# BOOSTXL-AUDIO_Main.net
KiCad netlist of a schematic drawn in Altium Designer
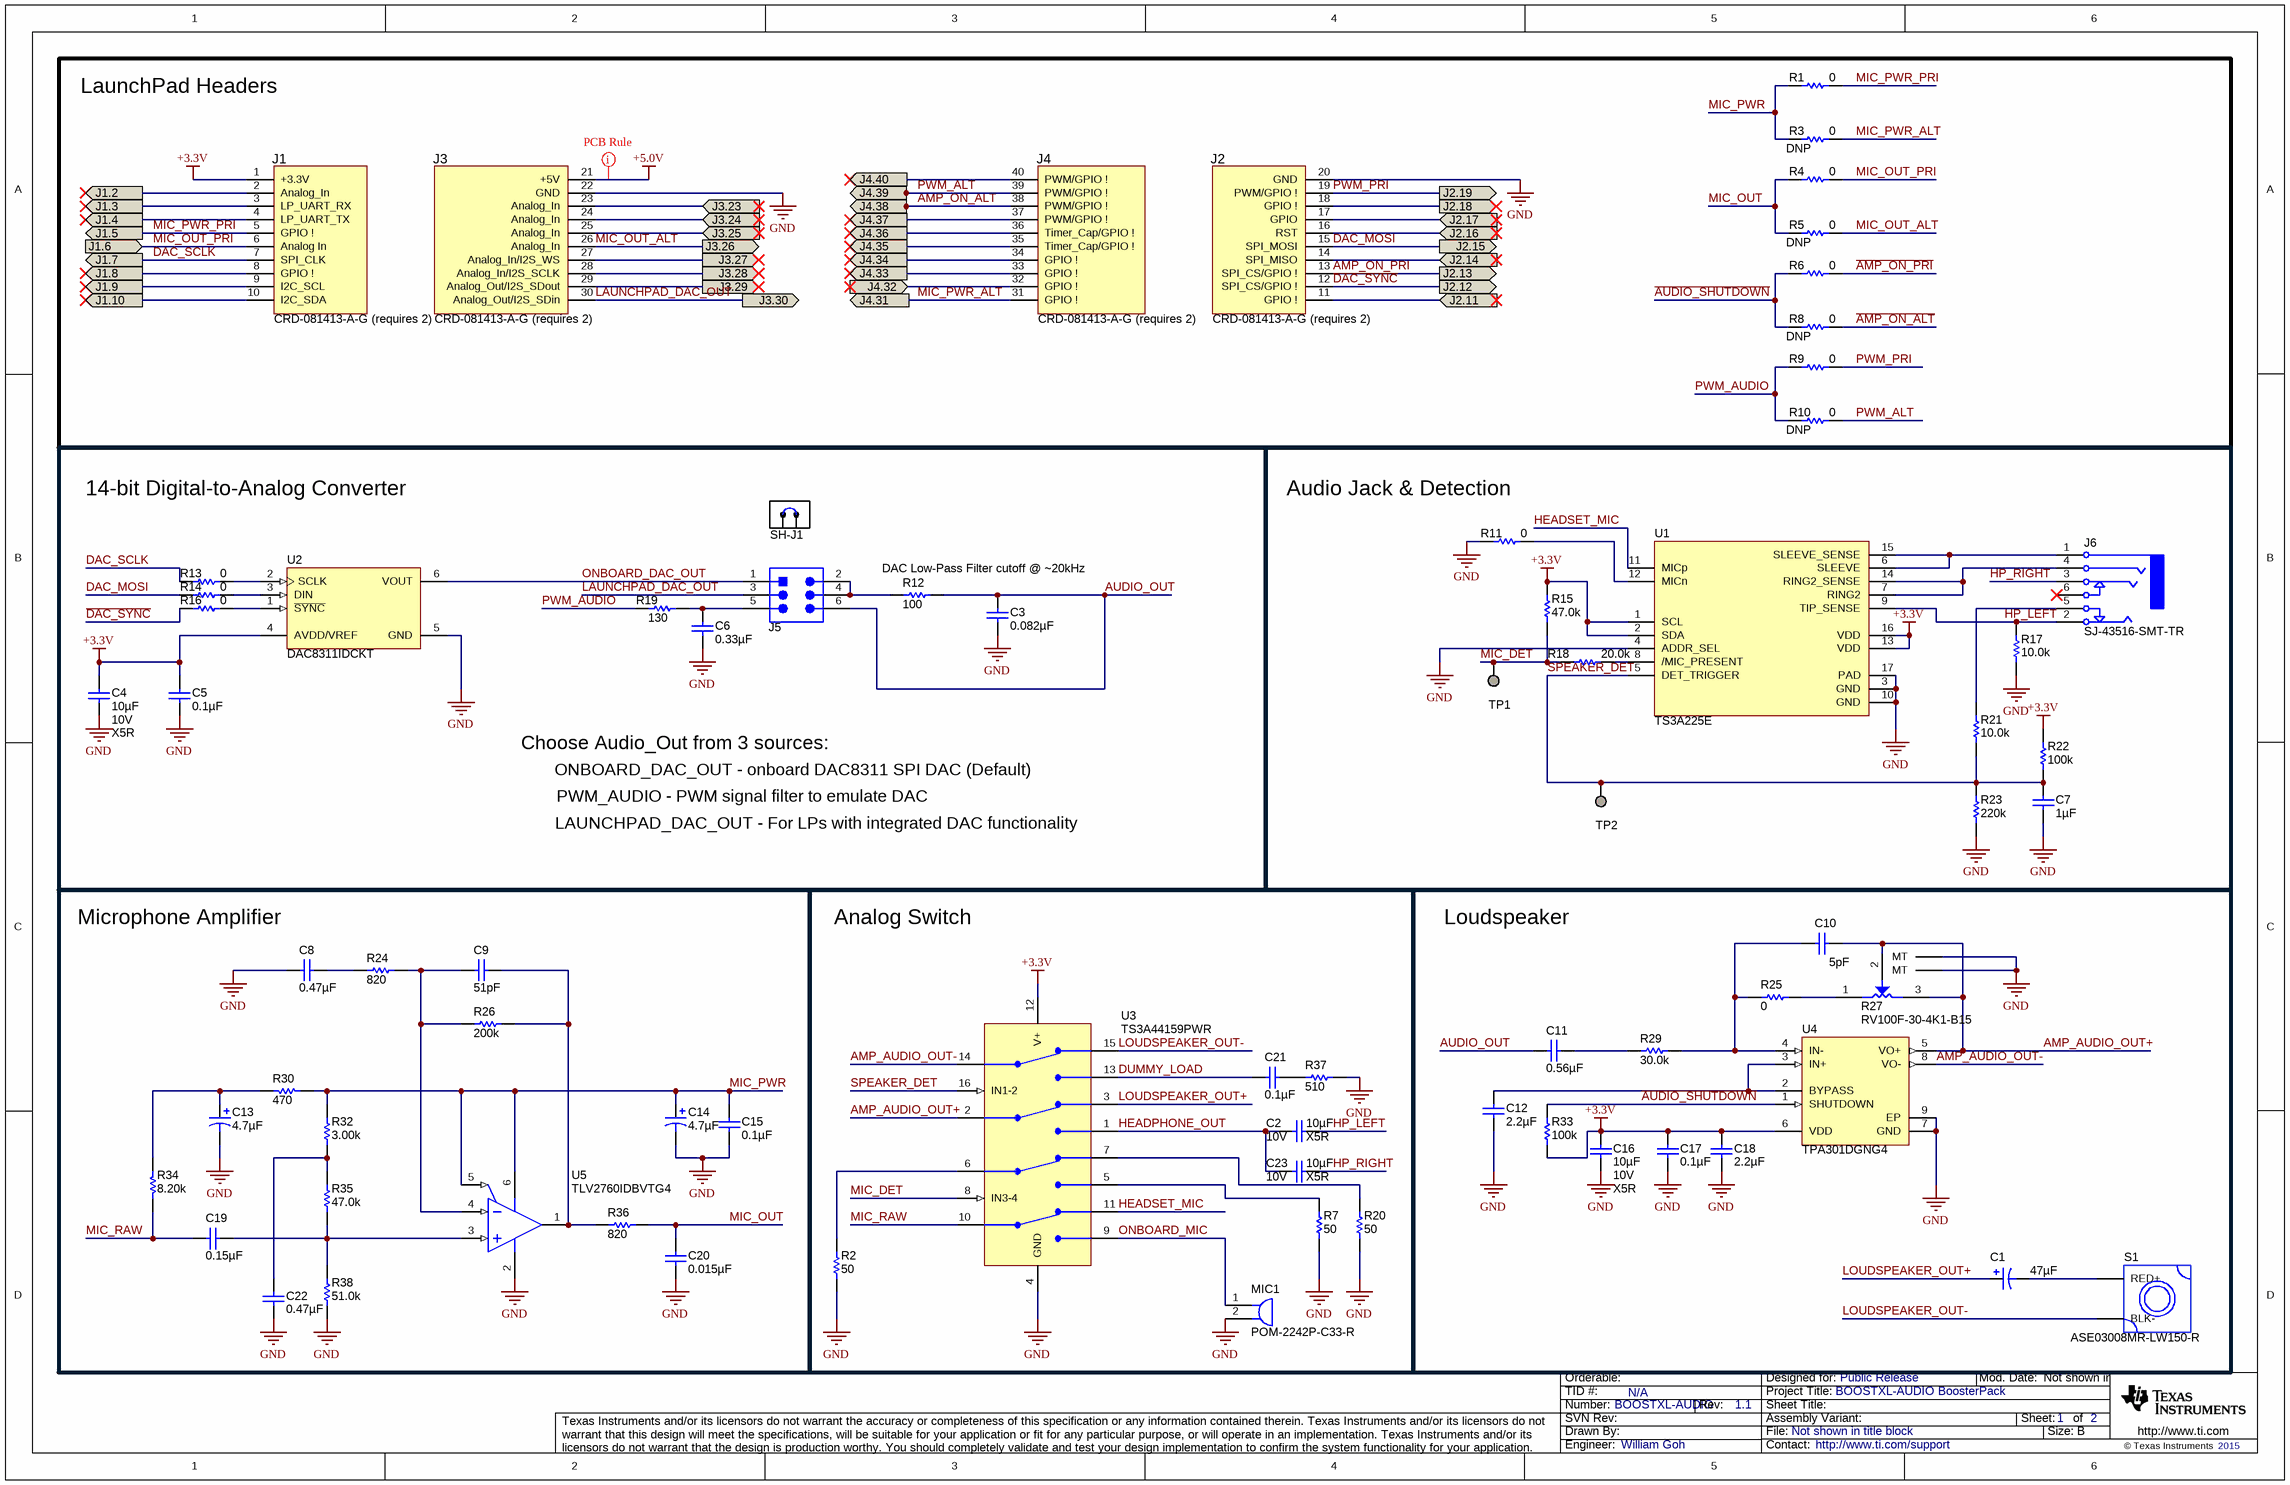
[diagram p0: BOOSTXL-AUDIO_Main.SchDoc]

(export (version "E")
  (design (tool "Eeschema 10.0.6"))
  (components
    (comp (ref "C1")
      (value "TPSB476K010R0250")
      (footprint "3528-21")
      (description "CAP, TA, 47 µF, 10 V, +/- 10%, 0.25 ohm, SMD")
      (fields
        (field (name "VALUEDISPLAYED") "47µF")
        (field (name "MANUFACTURER") "AVX")
        (field (name "PUBLISHER") "Texas Instruments")
      )
      (libsource (lib "Capacitor_Tantalum") (part "TPSB476K010R0250"))
    )
    (comp (ref "C2")
      (value "C1608X5R1A106M")
      (footprint "0603")
      (description "CAP, CERM, 10 µF, 10 V, +/- 20%, X5R, 0603")
      (fields
        (field (name "VALUEDISPLAYED") "10µF")
        (field (name "MANUFACTURER") "TDK")
        (field (name "VALUE2") "10V")
        (field (name "TEMPCO") "X5R")
        (field (name "PUBLISHER") "Texas Instruments")
      )
      (libsource (lib "Capacitor_Ceramic") (part "C1608X5R1A106M"))
    )
    (comp (ref "C3")
      (value "GRM188R71C823KA01D")
      (footprint "0603")
      (description "CAP, CERM, 0.082 µF, 16 V, +/- 10%, X7R, 0603")
      (fields
        (field (name "VALUEDISPLAYED") "0.082µF")
        (field (name "MANUFACTURER") "MuRata")
        (field (name "PUBLISHER") "Texas Instruments")
      )
      (libsource (lib "Capacitor_Ceramic") (part "GRM188R71C823KA01D"))
    )
    (comp (ref "C4")
      (value "C1608X5R1A106M")
      (footprint "0603")
      (description "CAP, CERM, 10 µF, 10 V, +/- 20%, X5R, 0603")
      (fields
        (field (name "VALUEDISPLAYED") "10µF")
        (field (name "MANUFACTURER") "TDK")
        (field (name "VALUE2") "10V")
        (field (name "TEMPCO") "X5R")
        (field (name "PUBLISHER") "Texas Instruments")
      )
      (libsource (lib "Capacitor_Ceramic") (part "C1608X5R1A106M"))
    )
    (comp (ref "C5")
      (value "GRM188R70J104KA01D")
      (footprint "0603")
      (description "CAP, CERM, 0.1uF, 6.3V, +/-10%, X7R, 0603")
      (fields
        (field (name "VALUEDISPLAYED") "0.1µF")
        (field (name "MANUFACTURER") "MuRata")
        (field (name "PUBLISHER") "Texas Instruments")
      )
      (libsource (lib "Capacitor_Ceramic") (part "GRM188R70J104KA01D"))
    )
    (comp (ref "C6")
      (value "C0603C334K8RACTU")
      (footprint "0603")
      (description "CAP, CERM, 0.33 µF, 10 V, +/- 10%, X7R, 0603")
      (fields
        (field (name "VALUEDISPLAYED") "0.33µF")
        (field (name "MANUFACTURER") "Kemet")
        (field (name "PUBLISHER") "Texas Instruments")
      )
      (libsource (lib "Capacitor_Ceramic") (part "C0603C334K8RACTU"))
    )
    (comp (ref "C7")
      (value "GRM188R71C105KA12D")
      (footprint "0603")
      (description "CAP, CERM, 1 µF, 16 V, +/- 10%, X7R, 0603")
      (fields
        (field (name "VALUEDISPLAYED") "1µF")
        (field (name "MANUFACTURER") "MuRata")
        (field (name "PUBLISHER") "Texas Instruments")
      )
      (libsource (lib "Capacitor_Ceramic") (part "GRM188R71C105KA12D"))
    )
    (comp (ref "C8")
      (value "GRM188R60J474KA01D")
      (footprint "0603")
      (description "CAP, CERM, 0.47uF, 6.3V, +/-10%, X5R, 0603")
      (fields
        (field (name "VALUEDISPLAYED") "0.47µF")
        (field (name "MANUFACTURER") "MuRata")
        (field (name "PUBLISHER") "Texas Instruments")
      )
      (libsource (lib "Capacitor_Ceramic") (part "GRM188R60J474KA01D"))
    )
    (comp (ref "C9")
      (value "GRM1885C2A510JA01D")
      (footprint "0603")
      (description "CAP, CERM, 51 pF, 100 V, +/- 5%, C0G/NP0, 0603")
      (fields
        (field (name "VALUEDISPLAYED") "51pF")
        (field (name "MANUFACTURER") "MuRata")
        (field (name "PUBLISHER") "Texas Instruments")
      )
      (libsource (lib "Capacitor_Ceramic") (part "GRM1885C2A510JA01D"))
    )
    (comp (ref "C10")
      (value "CC0603CRNPO9BN5R0")
      (footprint "0603")
      (description "CAP, CERM, 5 pF, 50 V, +/- 5%, C0G/NP0, 0603")
      (fields
        (field (name "MANUFACTURER") "Yageo America")
        (field (name "VALUEDISPLAYED") "5pF")
        (field (name "PUBLISHER") "Texas Instruments")
      )
      (libsource (lib "MiscParts") (part "Capacitor"))
    )
    (comp (ref "C11")
      (value "GRM188R71A564KA61D")
      (footprint "0603")
      (description "CAP, CERM, 0.56 µF, 10 V, +/- 10%, X7R, 0603")
      (fields
        (field (name "VALUEDISPLAYED") "0.56µF")
        (field (name "MANUFACTURER") "MuRata")
        (field (name "PUBLISHER") "Texas Instruments")
      )
      (libsource (lib "Capacitor_Ceramic") (part "GRM188R71A564KA61D"))
    )
    (comp (ref "C12")
      (value "GRM188R61A225KE34D")
      (footprint "0603")
      (description "CAP, CERM, 2.2 µF, 10 V, +/- 10%, X5R, 0603")
      (fields
        (field (name "VALUEDISPLAYED") "2.2µF")
        (field (name "MANUFACTURER") "MuRata")
        (field (name "PUBLISHER") "Texas Instruments")
      )
      (libsource (lib "Capacitor_Ceramic") (part "GRM188R61A225KE34D"))
    )
    (comp (ref "C13")
      (value "TPSA475K010R1400")
      (footprint "3216-18")
      (description "CAP, TA, 4.7 µF, 10 V, +/- 10%, 1.4 ohm, SMD")
      (fields
        (field (name "VALUEDISPLAYED") "4.7µF")
        (field (name "MANUFACTURER") "AVX")
        (field (name "PUBLISHER") "Texas Instruments")
      )
      (libsource (lib "Capacitor_Tantalum") (part "TPSA475K010R1400"))
    )
    (comp (ref "C14")
      (value "TPSA475K010R1400")
      (footprint "3216-18")
      (description "CAP, TA, 4.7 µF, 10 V, +/- 10%, 1.4 ohm, SMD")
      (fields
        (field (name "VALUEDISPLAYED") "4.7µF")
        (field (name "MANUFACTURER") "AVX")
        (field (name "PUBLISHER") "Texas Instruments")
      )
      (libsource (lib "Capacitor_Tantalum") (part "TPSA475K010R1400"))
    )
    (comp (ref "C15")
      (value "GRM188R70J104KA01D")
      (footprint "0603")
      (description "CAP, CERM, 0.1uF, 6.3V, +/-10%, X7R, 0603")
      (fields
        (field (name "VALUEDISPLAYED") "0.1µF")
        (field (name "MANUFACTURER") "MuRata")
        (field (name "PUBLISHER") "Texas Instruments")
      )
      (libsource (lib "Capacitor_Ceramic") (part "GRM188R70J104KA01D"))
    )
    (comp (ref "C16")
      (value "C1608X5R1A106M")
      (footprint "0603")
      (description "CAP, CERM, 10 µF, 10 V, +/- 20%, X5R, 0603")
      (fields
        (field (name "VALUEDISPLAYED") "10µF")
        (field (name "MANUFACTURER") "TDK")
        (field (name "VALUE2") "10V")
        (field (name "TEMPCO") "X5R")
        (field (name "PUBLISHER") "Texas Instruments")
      )
      (libsource (lib "Capacitor_Ceramic") (part "C1608X5R1A106M"))
    )
    (comp (ref "C17")
      (value "GRM188R70J104KA01D")
      (footprint "0603")
      (description "CAP, CERM, 0.1uF, 6.3V, +/-10%, X7R, 0603")
      (fields
        (field (name "VALUEDISPLAYED") "0.1µF")
        (field (name "MANUFACTURER") "MuRata")
        (field (name "PUBLISHER") "Texas Instruments")
      )
      (libsource (lib "Capacitor_Ceramic") (part "GRM188R70J104KA01D"))
    )
    (comp (ref "C18")
      (value "GRM188R61A225KE34D")
      (footprint "0603")
      (description "CAP, CERM, 2.2 µF, 10 V, +/- 10%, X5R, 0603")
      (fields
        (field (name "VALUEDISPLAYED") "2.2µF")
        (field (name "MANUFACTURER") "MuRata")
        (field (name "PUBLISHER") "Texas Instruments")
      )
      (libsource (lib "Capacitor_Ceramic") (part "GRM188R61A225KE34D"))
    )
    (comp (ref "C19")
      (value "GRM188R61A154KA01D")
      (footprint "0603")
      (description "CAP, CERM, 0.15uF, 10V, +/-10%, X5R, 0603")
      (fields
        (field (name "VALUEDISPLAYED") "0.15µF")
        (field (name "MANUFACTURER") "MuRata")
        (field (name "PUBLISHER") "Texas Instruments")
      )
      (libsource (lib "Capacitor_Ceramic") (part "GRM188R61A154KA01D"))
    )
    (comp (ref "C20")
      (value "C0603C153K1RACTU")
      (footprint "0603")
      (description "CAP, CERM, 0.015 µF, 100 V, +/- 10%, X7R, 0603")
      (fields
        (field (name "VALUEDISPLAYED") "0.015µF")
        (field (name "MANUFACTURER") "Kemet")
        (field (name "PUBLISHER") "Texas Instruments")
      )
      (libsource (lib "Capacitor_Ceramic") (part "C0603C153K1RACTU"))
    )
    (comp (ref "C21")
      (value "GRM188R70J104KA01D")
      (footprint "0603")
      (description "CAP, CERM, 0.1uF, 6.3V, +/-10%, X7R, 0603")
      (fields
        (field (name "VALUEDISPLAYED") "0.1µF")
        (field (name "MANUFACTURER") "MuRata")
        (field (name "PUBLISHER") "Texas Instruments")
      )
      (libsource (lib "Capacitor_Ceramic") (part "GRM188R70J104KA01D"))
    )
    (comp (ref "C22")
      (value "GRM188R60J474KA01D")
      (footprint "0603")
      (description "CAP, CERM, 0.47uF, 6.3V, +/-10%, X5R, 0603")
      (fields
        (field (name "VALUEDISPLAYED") "0.47µF")
        (field (name "MANUFACTURER") "MuRata")
        (field (name "PUBLISHER") "Texas Instruments")
      )
      (libsource (lib "Capacitor_Ceramic") (part "GRM188R60J474KA01D"))
    )
    (comp (ref "C23")
      (value "C1608X5R1A106M")
      (footprint "0603")
      (description "CAP, CERM, 10 µF, 10 V, +/- 20%, X5R, 0603")
      (fields
        (field (name "VALUEDISPLAYED") "10µF")
        (field (name "MANUFACTURER") "TDK")
        (field (name "VALUE2") "10V")
        (field (name "TEMPCO") "X5R")
        (field (name "PUBLISHER") "Texas Instruments")
      )
      (libsource (lib "Capacitor_Ceramic") (part "C1608X5R1A106M"))
    )
    (comp (ref "J1")
      (value "CRD-081413-A-G (requires 2)")
      (footprint "40Pin BP")
      (description "40Pin Booster Pack Connection")
      (fields (field (name "MANUFACTURER") "MLE") (field (name "SYMBOLCREATOR") "a0272566"))
      (libsource (lib "MP_Library") (part "40Pin Booster Pack Connection"))
    )
    (comp (ref "J5")
      (value "PBC03DAAN")
      (footprint "Sullins_PBC03DAAN")
      (description "Header, 100mil, 3x2, Gold, TH")
      (fields
        (field (name "MANUFACTURER") "Sullins Connector Solutions")
        (field (name "SYMBOLCREATOR") "a0412235")
        (field (name "PUBLISHER") "Texas Instruments")
      )
      (libsource (lib "Connectors_Sullins") (part "PBC03DAAN"))
    )
    (comp (ref "J6")
      (value "SJ-43516-SMT-TR")
      (footprint "CUI_SJ-43516-SMT")
      (description "AUDIO JACK 3.5mm 4COND, SMT")
      (fields
        (field (name "MANUFACTURER") "CUI Inc.")
        (field (name "SYMBOLCREATOR") "Altium")
        (field (name "PUBLISHER") "Texas Instruments")
      )
      (libsource (lib "Connectors_Other") (part "SJ-43516-SMT-TR"))
    )
    (comp (ref "MIC1")
      (value "POM-2242P-C33-R")
      (footprint "MIC_POM-2242P-C33-R")
      (description "Microphone, Condenser, Analog, Omnidirectional, -42DB, TH")
      (fields
        (field (name "MANUFACTURER") "PUI Audio")
        (field (name "SYMBOLCREATOR") "a0412235")
        (field (name "PUBLISHER") "Texas Instruments")
      )
      (libsource (lib "Other_Passive") (part "POM-2242P-C33-R"))
    )
    (comp (ref "R1")
      (value "CRCW06030000Z0EA")
      (footprint "0603")
      (description "RES, 0, 5%, 0.1 W, 0603")
      (fields
        (field (name "VALUEDISPLAYED") "0")
        (field (name "MANUFACTURER") "Vishay-Dale")
        (field (name "PUBLISHER") "Texas Instruments")
      )
      (libsource (lib "Resistor_0603") (part "CRCW06030000Z0EA"))
    )
    (comp (ref "R2")
      (value "CRCW060350R0FKEA")
      (footprint "0603")
      (description "RES, 50, 1%, 0.1 W, 0603")
      (fields
        (field (name "VALUEDISPLAYED") "50")
        (field (name "MANUFACTURER") "Vishay-Dale")
        (field (name "PUBLISHER") "Texas Instruments")
      )
      (libsource (lib "Resistor_0603") (part "CRCW060350R0FKEA"))
    )
    (comp (ref "R3")
      (value "CRCW06030000Z0EA")
      (footprint "0603")
      (description "RES, 0, 5%, 0.1 W, 0603")
      (fields
        (field (name "VALUEDISPLAYED") "0")
        (field (name "MANUFACTURER") "Vishay-Dale")
        (field (name "DNP") "DNP")
        (field (name "PUBLISHER") "Texas Instruments")
      )
      (libsource (lib "Resistor_0603") (part "CRCW06030000Z0EA"))
    )
    (comp (ref "R4")
      (value "CRCW06030000Z0EA")
      (footprint "0603")
      (description "RES, 0, 5%, 0.1 W, 0603")
      (fields
        (field (name "VALUEDISPLAYED") "0")
        (field (name "MANUFACTURER") "Vishay-Dale")
        (field (name "PUBLISHER") "Texas Instruments")
      )
      (libsource (lib "Resistor_0603") (part "CRCW06030000Z0EA"))
    )
    (comp (ref "R5")
      (value "CRCW06030000Z0EA")
      (footprint "0603")
      (description "RES, 0, 5%, 0.1 W, 0603")
      (fields
        (field (name "VALUEDISPLAYED") "0")
        (field (name "MANUFACTURER") "Vishay-Dale")
        (field (name "DNP") "DNP")
        (field (name "PUBLISHER") "Texas Instruments")
      )
      (libsource (lib "Resistor_0603") (part "CRCW06030000Z0EA"))
    )
    (comp (ref "R6")
      (value "CRCW06030000Z0EA")
      (footprint "0603")
      (description "RES, 0, 5%, 0.1 W, 0603")
      (fields
        (field (name "VALUEDISPLAYED") "0")
        (field (name "MANUFACTURER") "Vishay-Dale")
        (field (name "PUBLISHER") "Texas Instruments")
      )
      (libsource (lib "Resistor_0603") (part "CRCW06030000Z0EA"))
    )
    (comp (ref "R7")
      (value "CRCW060350R0FKEA")
      (footprint "0603")
      (description "RES, 50, 1%, 0.1 W, 0603")
      (fields
        (field (name "VALUEDISPLAYED") "50")
        (field (name "MANUFACTURER") "Vishay-Dale")
        (field (name "PUBLISHER") "Texas Instruments")
      )
      (libsource (lib "Resistor_0603") (part "CRCW060350R0FKEA"))
    )
    (comp (ref "R8")
      (value "CRCW06030000Z0EA")
      (footprint "0603")
      (description "RES, 0, 5%, 0.1 W, 0603")
      (fields
        (field (name "VALUEDISPLAYED") "0")
        (field (name "MANUFACTURER") "Vishay-Dale")
        (field (name "DNP") "DNP")
        (field (name "PUBLISHER") "Texas Instruments")
      )
      (libsource (lib "Resistor_0603") (part "CRCW06030000Z0EA"))
    )
    (comp (ref "R9")
      (value "CRCW06030000Z0EA")
      (footprint "0603")
      (description "RES, 0, 5%, 0.1 W, 0603")
      (fields
        (field (name "VALUEDISPLAYED") "0")
        (field (name "MANUFACTURER") "Vishay-Dale")
        (field (name "PUBLISHER") "Texas Instruments")
      )
      (libsource (lib "Resistor_0603") (part "CRCW06030000Z0EA"))
    )
    (comp (ref "R10")
      (value "CRCW06030000Z0EA")
      (footprint "0603")
      (description "RES, 0, 5%, 0.1 W, 0603")
      (fields
        (field (name "VALUEDISPLAYED") "0")
        (field (name "MANUFACTURER") "Vishay-Dale")
        (field (name "DNP") "DNP")
        (field (name "PUBLISHER") "Texas Instruments")
      )
      (libsource (lib "Resistor_0603") (part "CRCW06030000Z0EA"))
    )
    (comp (ref "R11")
      (value "CRCW06030000Z0EA")
      (footprint "0603")
      (description "RES, 0, 5%, 0.1 W, 0603")
      (fields
        (field (name "VALUEDISPLAYED") "0")
        (field (name "MANUFACTURER") "Vishay-Dale")
        (field (name "PUBLISHER") "Texas Instruments")
      )
      (libsource (lib "Resistor_0603") (part "CRCW06030000Z0EA"))
    )
    (comp (ref "R12")
      (value "RC0603FR-07100RL")
      (footprint "0603")
      (description "RES, 100, 1%, 0.1 W, 0603")
      (fields
        (field (name "VALUEDISPLAYED") "100")
        (field (name "MANUFACTURER") "Yageo America")
        (field (name "PUBLISHER") "Texas Instruments")
      )
      (libsource (lib "Resistor_0603") (part "RC0603FR-07100RL"))
    )
    (comp (ref "R13")
      (value "CRCW06030000Z0EA")
      (footprint "0603")
      (description "RES, 0, 5%, 0.1 W, 0603")
      (fields
        (field (name "VALUEDISPLAYED") "0")
        (field (name "MANUFACTURER") "Vishay-Dale")
        (field (name "PUBLISHER") "Texas Instruments")
      )
      (libsource (lib "Resistor_0603") (part "CRCW06030000Z0EA"))
    )
    (comp (ref "R14")
      (value "CRCW06030000Z0EA")
      (footprint "0603")
      (description "RES, 0, 5%, 0.1 W, 0603")
      (fields
        (field (name "VALUEDISPLAYED") "0")
        (field (name "MANUFACTURER") "Vishay-Dale")
        (field (name "PUBLISHER") "Texas Instruments")
      )
      (libsource (lib "Resistor_0603") (part "CRCW06030000Z0EA"))
    )
    (comp (ref "R15")
      (value "RC0603FR-0747KL")
      (footprint "0603")
      (description "RES, 47.0 k, 1%, 0.1 W, 0603")
      (fields
        (field (name "VALUEDISPLAYED") "47.0k")
        (field (name "MANUFACTURER") "Yageo America")
        (field (name "PUBLISHER") "Texas Instruments")
      )
      (libsource (lib "Resistor_0603") (part "RC0603FR-0747KL"))
    )
    (comp (ref "R16")
      (value "CRCW06030000Z0EA")
      (footprint "0603")
      (description "RES, 0, 5%, 0.1 W, 0603")
      (fields
        (field (name "VALUEDISPLAYED") "0")
        (field (name "MANUFACTURER") "Vishay-Dale")
        (field (name "PUBLISHER") "Texas Instruments")
      )
      (libsource (lib "Resistor_0603") (part "CRCW06030000Z0EA"))
    )
    (comp (ref "R17")
      (value "RC0603FR-0710KL")
      (footprint "0603")
      (description "RES, 10.0 k, 1%, 0.1 W, 0603")
      (fields
        (field (name "VALUEDISPLAYED") "10.0k")
        (field (name "MANUFACTURER") "Yageo America")
        (field (name "PUBLISHER") "Texas Instruments")
      )
      (libsource (lib "Resistor_0603") (part "RC0603FR-0710KL"))
    )
    (comp (ref "R18")
      (value "RC0603FR-0720KL")
      (footprint "0603")
      (description "RES, 20.0 k, 1%, 0.1 W, 0603")
      (fields
        (field (name "VALUEDISPLAYED") "20.0k")
        (field (name "MANUFACTURER") "Yageo America")
        (field (name "PUBLISHER") "Texas Instruments")
      )
      (libsource (lib "Resistor_0603") (part "RC0603FR-0720KL"))
    )
    (comp (ref "R19")
      (value "RC0603FR-07130RL")
      (footprint "0603")
      (description "RES, 130, 1%, 0.1 W, 0603")
      (fields
        (field (name "VALUEDISPLAYED") "130")
        (field (name "MANUFACTURER") "Yageo America")
        (field (name "PUBLISHER") "Texas Instruments")
      )
      (libsource (lib "Resistor_0603") (part "RC0603FR-07130RL"))
    )
    (comp (ref "R20")
      (value "CRCW060350R0FKEA")
      (footprint "0603")
      (description "RES, 50, 1%, 0.1 W, 0603")
      (fields
        (field (name "VALUEDISPLAYED") "50")
        (field (name "MANUFACTURER") "Vishay-Dale")
        (field (name "PUBLISHER") "Texas Instruments")
      )
      (libsource (lib "Resistor_0603") (part "CRCW060350R0FKEA"))
    )
    (comp (ref "R21")
      (value "RC0603FR-0710KL")
      (footprint "0603")
      (description "RES, 10.0 k, 1%, 0.1 W, 0603")
      (fields
        (field (name "VALUEDISPLAYED") "10.0k")
        (field (name "MANUFACTURER") "Yageo America")
        (field (name "PUBLISHER") "Texas Instruments")
      )
      (libsource (lib "Resistor_0603") (part "RC0603FR-0710KL"))
    )
    (comp (ref "R22")
      (value "CRCW0603100KFKEA")
      (footprint "0603")
      (description "RES, 100 k, 1%, 0.1 W, 0603")
      (fields
        (field (name "VALUEDISPLAYED") "100k")
        (field (name "MANUFACTURER") "Vishay-Dale")
        (field (name "PUBLISHER") "Texas Instruments")
      )
      (libsource (lib "Resistor_0603") (part "CRCW0603100KFKEA"))
    )
    (comp (ref "R23")
      (value "RC0603FR-07220KL")
      (footprint "0603")
      (description "RES, 220 k, 1%, 0.1 W, 0603")
      (fields
        (field (name "VALUEDISPLAYED") "220k")
        (field (name "MANUFACTURER") "Yageo America")
        (field (name "PUBLISHER") "Texas Instruments")
      )
      (libsource (lib "Resistor_0603") (part "RC0603FR-07220KL"))
    )
    (comp (ref "R24")
      (value "820")
      (footprint "0603")
      (description "RES, 820 ohm, 1%, 0.1W, 0603")
      (fields
        (field (name "PARTNUMBER") "RC0603FR-07820RL")
        (field (name "MANUFACTURER") "Yageo America")
        (field (name "PUBLISHER") "Texas Instruments")
      )
      (libsource (lib "Resistor_0603") (part "RC0603FR-07820RL"))
    )
    (comp (ref "R25")
      (value "CRCW06030000Z0EA")
      (footprint "0603")
      (description "RES, 0, 5%, 0.1 W, 0603")
      (fields
        (field (name "VALUEDISPLAYED") "0")
        (field (name "MANUFACTURER") "Vishay-Dale")
        (field (name "PUBLISHER") "Texas Instruments")
      )
      (libsource (lib "Resistor_0603") (part "CRCW06030000Z0EA"))
    )
    (comp (ref "R26")
      (value "RC0603FR-07200KL")
      (footprint "0603")
      (description "RES, 200 k, 1%, 0.1 W, 0603")
      (fields
        (field (name "VALUEDISPLAYED") "200k")
        (field (name "MANUFACTURER") "Yageo America")
        (field (name "PUBLISHER") "Texas Instruments")
      )
      (libsource (lib "Resistor_0603") (part "RC0603FR-07200KL"))
    )
    (comp (ref "R27")
      (value "RV100F-30-4K1-B15")
      (footprint "RV100F-30-4K1-B15")
      (description "Potentiometers 10mm Linear 100K PC Mount")
      (fields
        (field (name "MANUFACTURER") "Alpha (Taiwan)")
        (field (name "ALTERNATE PARTNUMBER") "Equivalent")
        (field (name "PUBLISHER") "Texas Instruments")
      )
      (libsource (lib "MSP430 Apps Component Library") (part "RV100F-30-4K1-B15"))
    )
    (comp (ref "R29")
      (value "RC0603FR-0730KL")
      (footprint "0603")
      (description "RES, 30.0 k, 1%, 0.1 W, 0603")
      (fields
        (field (name "VALUEDISPLAYED") "30.0k")
        (field (name "MANUFACTURER") "Yageo America")
        (field (name "PUBLISHER") "Texas Instruments")
      )
      (libsource (lib "Resistor_0603") (part "RC0603FR-0730KL"))
    )
    (comp (ref "R30")
      (value "470")
      (footprint "0603")
      (description "RES, 470 ohm, 1%, 0.1W, 0603")
      (fields
        (field (name "PARTNUMBER") "RC0603FR-07470RL")
        (field (name "MANUFACTURER") "Yageo America")
        (field (name "PUBLISHER") "Texas Instruments")
      )
      (libsource (lib "Resistor_0603") (part "RC0603FR-07470RL"))
    )
    (comp (ref "R32")
      (value "RC0603FR-073KL")
      (footprint "0603")
      (description "RES, 3.00 k, 1%, 0.1 W, 0603")
      (fields
        (field (name "VALUEDISPLAYED") "3.00k")
        (field (name "MANUFACTURER") "Yageo America")
        (field (name "PUBLISHER") "Texas Instruments")
      )
      (libsource (lib "Resistor_0603") (part "RC0603FR-073KL"))
    )
    (comp (ref "R33")
      (value "CRCW0603100KFKEA")
      (footprint "0603")
      (description "RES, 100 k, 1%, 0.1 W, 0603")
      (fields
        (field (name "VALUEDISPLAYED") "100k")
        (field (name "MANUFACTURER") "Vishay-Dale")
        (field (name "PUBLISHER") "Texas Instruments")
      )
      (libsource (lib "Resistor_0603") (part "CRCW0603100KFKEA"))
    )
    (comp (ref "R34")
      (value "8.20k")
      (footprint "0603")
      (description "RES, 8.20k ohm, 1%, 0.1W, 0603")
      (fields
        (field (name "PARTNUMBER") "RC0603FR-078K2L")
        (field (name "MANUFACTURER") "Yageo America")
        (field (name "PUBLISHER") "Texas Instruments")
      )
      (libsource (lib "Resistor_0603") (part "RC0603FR-078K2L"))
    )
    (comp (ref "R35")
      (value "RC0603FR-0747KL")
      (footprint "0603")
      (description "RES, 47.0 k, 1%, 0.1 W, 0603")
      (fields
        (field (name "VALUEDISPLAYED") "47.0k")
        (field (name "MANUFACTURER") "Yageo America")
        (field (name "PUBLISHER") "Texas Instruments")
      )
      (libsource (lib "Resistor_0603") (part "RC0603FR-0747KL"))
    )
    (comp (ref "R36")
      (value "820")
      (footprint "0603")
      (description "RES, 820 ohm, 1%, 0.1W, 0603")
      (fields
        (field (name "PARTNUMBER") "RC0603FR-07820RL")
        (field (name "MANUFACTURER") "Yageo America")
        (field (name "PUBLISHER") "Texas Instruments")
      )
      (libsource (lib "Resistor_0603") (part "RC0603FR-07820RL"))
    )
    (comp (ref "R37")
      (value "RC0603FR-07510RL")
      (footprint "0603")
      (description "RES, 510, 1%, 0.1 W, 0603")
      (fields
        (field (name "VALUEDISPLAYED") "510")
        (field (name "MANUFACTURER") "Yageo America")
        (field (name "PUBLISHER") "Texas Instruments")
      )
      (libsource (lib "Resistor_0603") (part "RC0603FR-07510RL"))
    )
    (comp (ref "R38")
      (value "RC0603FR-0751KL")
      (footprint "0603")
      (description "RES, 51.0 k, 1%, 0.1 W, 0603")
      (fields
        (field (name "VALUEDISPLAYED") "51.0k")
        (field (name "MANUFACTURER") "Yageo America")
        (field (name "PUBLISHER") "Texas Instruments")
      )
      (libsource (lib "Resistor_0603") (part "RC0603FR-0751KL"))
    )
    (comp (ref "S1")
      (value "ASE03008MR-LW150-R")
      (footprint "ASE03008MR-LW150-R")
      (description "PUI SPEAKER ENCLOSURE 1 W 8 OHM 83 D")
      (fields
        (field (name "MANUFACTURER") "PUI Audio")
        (field (name "SYMBOLCREATOR") "a0866890")
        (field (name "PUBLISHER") "Texas Instruments")
      )
      (libsource (lib "MSP430 Apps Component Library") (part "PUI Speaker Enclosure"))
    )
    (comp (ref "SH-J1")
      (value "969102-0000-DA")
      (footprint "SNT-100-BK-G")
      (description "Shunt, 100mil, Gold plated, Black")
      (fields
        (field (name "MANUFACTURER") "3M")
        (field (name "ALTERNATE PARTNUMBER") "SNT-100-BK-G")
        (field (name "PUBLISHER") "Texas Instruments")
      )
      (libsource (lib "Hardware") (part "969102-0000-DA"))
    )
    (comp (ref "TP1")
      (value "TESTPOINT")
      (footprint "TP_H045P075")
      (description "Testpoint")
      (fields
        (field (name "MANUFACTURER") "Texas Instruments")
        (field (name "PARTNUMBER") "TP_H0.45P0.75")
        (field (name "PUBLISHER") "Texas Instruments")
      )
      (libsource (lib "Hardware") (part "TP_H0.45P0.75"))
    )
    (comp (ref "TP2")
      (value "TESTPOINT")
      (footprint "TP_H045P075")
      (description "Testpoint")
      (fields
        (field (name "MANUFACTURER") "Texas Instruments")
        (field (name "PARTNUMBER") "TP_H0.45P0.75")
        (field (name "PUBLISHER") "Texas Instruments")
      )
      (libsource (lib "Hardware") (part "TP_H0.45P0.75"))
    )
    (comp (ref "U1")
      (value "TS3A225E")
      (footprint "QFN-16 (RTE)")
      (description "Autonomous Audio Switch with Headset Type Detection")
      (fields (field (name "MANUFACTURER") "Texas Instruments") (field (name "SYMBOLCREATOR") "Use LDAP id"))
      (libsource (lib "MSP430 Apps Component Library") (part "TS3A225E"))
    )
    (comp (ref "U2")
      (value "DAC8311IDCKT")
      (footprint "TI-DCK6_V")
      (fields (field (name "MANUFACTURER") "Texas Instruments"))
      (libsource (lib "Altium Content Vault") (part "TI-DAC8X11_X311DCK6"))
    )
    (comp (ref "U3")
      (value "TS3A44159PWR")
      (footprint "PW0016A_N")
      (fields
        (field (name "MANUFACTURER") "Texas Instruments")
        (field (name "SYMBOLCREATOR") "a0411947")
        (field (name "PUBLISHER") "Texas Instruments")
      )
      (libsource (lib "TI_Pre_Release") (part "TS3A44159PWR"))
    )
    (comp (ref "U4")
      (value "TPA301DGNG4")
      (footprint "TI-DGN8-1760X1425TP_M")
      (description "350-mW Mono Class-AB Audio Amplifier, -40 to 85 degC, 8-pin SOP (DGN8), Green (RoHS & no Sb/Br)")
      (fields (field (name "MANUFACTURER") "Texas Instruments"))
      (libsource (lib "Altium Content Vault") (part "TI-TPAXX1DGN8-1760X1430TP"))
    )
    (comp (ref "U5")
      (value "TLV2760IDBVTG4")
      (footprint "DBV0006A_N")
      (fields
        (field (name "MANUFACTURER") "Texas Instruments")
        (field (name "ALTERNATE PARTNUMBER") "Equivalent")
      )
      (libsource (lib "TI Amplifiers and Linear Operational Amplifier Precision Amplifier Part Two") (part "TLV2760IDBVTG4"))
    )
  )
  (nets
    (net (code "1") (name "+3.3V") (class "Default")
      (node (ref "C16") (pin "2") (pinfunction "2_2") (pintype "passive"))
      (node (ref "C17") (pin "2") (pinfunction "2_2") (pintype "passive"))
      (node (ref "C18") (pin "1") (pinfunction "1_1") (pintype "passive"))
      (node (ref "C4") (pin "1") (pinfunction "1_1") (pintype "passive"))
      (node (ref "C5") (pin "1") (pinfunction "1_1") (pintype "passive"))
      (node (ref "J1") (pin "1") (pinfunction "+3.3V_1") (pintype "power_in"))
      (node (ref "R15") (pin "1") (pinfunction "1_1") (pintype "passive"))
      (node (ref "R22") (pin "1") (pinfunction "1_1") (pintype "passive"))
      (node (ref "R33") (pin "1") (pinfunction "1_1") (pintype "passive"))
      (node (ref "U1") (pin "1") (pinfunction "SCL_1") (pintype "passive"))
      (node (ref "U1") (pin "13") (pinfunction "VDD_13") (pintype "passive"))
      (node (ref "U1") (pin "16") (pinfunction "VDD_16") (pintype "passive"))
      (node (ref "U1") (pin "2") (pinfunction "SDA_2") (pintype "passive"))
      (node (ref "U2") (pin "4") (pinfunction "AVDD/VREF_4") (pintype "power_in"))
      (node (ref "U3") (pin "12") (pinfunction "V+_12") (pintype "power_in"))
      (node (ref "U4") (pin "6") (pinfunction "VDD_6") (pintype "power_in"))
    )
    (net (code "2") (name "+5.0V") (class "Default")
      (node (ref "J1") (pin "21") (pinfunction "+5V_21") (pintype "power_in"))
    )
    (net (code "3") (name "/AMP_AUDIO_OUT+") (class "Default")
      (node (ref "C10") (pin "2") (pinfunction "2_2") (pintype "passive"))
      (node (ref "R27") (pin "2") (pinfunction "A2_2") (pintype "passive"))
      (node (ref "R27") (pin "3") (pinfunction "A3_3") (pintype "passive"))
      (node (ref "U3") (pin "2") (pinfunction "COM2_2") (pintype "passive"))
      (node (ref "U4") (pin "5") (pinfunction "VO+_5") (pintype "output"))
    )
    (net (code "4") (name "/AMP_AUDIO_OUT-") (class "Default")
      (node (ref "U3") (pin "14") (pinfunction "COM1_14") (pintype "passive"))
      (node (ref "U4") (pin "8") (pinfunction "VO-_8") (pintype "output"))
    )
    (net (code "5") (name "/AMP_ON_ALT") (class "Default")
      (node (ref "J1") (pin "38") (pinfunction "PWM/GPIO_!_38") (pintype "passive"))
      (node (ref "R8") (pin "2") (pinfunction "2_2") (pintype "passive"))
    )
    (net (code "6") (name "/AMP_ON_PRI") (class "Default")
      (node (ref "J1") (pin "13") (pinfunction "SPI_CS/GPIO_!_13") (pintype "passive"))
      (node (ref "R6") (pin "2") (pinfunction "2_2") (pintype "passive"))
    )
    (net (code "7") (name "/AUDIO_OUT") (class "Default")
      (node (ref "C11") (pin "2") (pinfunction "2_2") (pintype "passive"))
      (node (ref "C3") (pin "2") (pinfunction "2_2") (pintype "passive"))
      (node (ref "J5") (pin "6") (pinfunction "6_6") (pintype "passive"))
      (node (ref "R12") (pin "2") (pinfunction "2_2") (pintype "passive"))
    )
    (net (code "8") (name "/AUDIO_SHUTDOWN") (class "Default")
      (node (ref "R33") (pin "2") (pinfunction "2_2") (pintype "passive"))
      (node (ref "R6") (pin "1") (pinfunction "1_1") (pintype "passive"))
      (node (ref "R8") (pin "1") (pinfunction "1_1") (pintype "passive"))
      (node (ref "U4") (pin "1") (pinfunction "SHUTDOWN_1") (pintype "input"))
    )
    (net (code "9") (name "/DAC_MOSI") (class "Default")
      (node (ref "J1") (pin "15") (pinfunction "SPI_MOSI_15") (pintype "passive"))
      (node (ref "R14") (pin "1") (pinfunction "1_1") (pintype "passive"))
    )
    (net (code "10") (name "/DAC_SCLK") (class "Default")
      (node (ref "J1") (pin "7") (pinfunction "SPI_CLK_7") (pintype "passive"))
      (node (ref "R13") (pin "1") (pinfunction "1_1") (pintype "passive"))
    )
    (net (code "11") (name "/DAC_SYNC") (class "Default")
      (node (ref "J1") (pin "12") (pinfunction "SPI_CS/GPIO_!_12") (pintype "passive"))
      (node (ref "R16") (pin "1") (pinfunction "1_1") (pintype "passive"))
    )
    (net (code "12") (name "/DUMMY_LOAD") (class "Default")
      (node (ref "C21") (pin "2") (pinfunction "2_2") (pintype "passive"))
      (node (ref "U3") (pin "13") (pinfunction "NO1_13") (pintype "passive"))
    )
    (net (code "13") (name "/HEADPHONE_OUT") (class "Default")
      (node (ref "C2") (pin "1") (pinfunction "1_1") (pintype "passive"))
      (node (ref "C23") (pin "1") (pinfunction "1_1") (pintype "passive"))
      (node (ref "U3") (pin "1") (pinfunction "NO2_1") (pintype "passive"))
    )
    (net (code "14") (name "/HEADSET_MIC") (class "Default")
      (node (ref "U1") (pin "11") (pinfunction "MICp_11") (pintype "passive"))
      (node (ref "U3") (pin "11") (pinfunction "NC4_11") (pintype "passive"))
    )
    (net (code "15") (name "/HP_LEFT") (class "Default")
      (node (ref "C2") (pin "2") (pinfunction "2_2") (pintype "passive"))
      (node (ref "J6") (pin "2") (pinfunction "TIP_2") (pintype "passive"))
      (node (ref "R17") (pin "1") (pinfunction "1_1") (pintype "passive"))
      (node (ref "U1") (pin "9") (pinfunction "TIP_SENSE_9") (pintype "passive"))
    )
    (net (code "16") (name "/HP_RIGHT") (class "Default")
      (node (ref "C23") (pin "2") (pinfunction "2_2") (pintype "passive"))
      (node (ref "J6") (pin "3") (pinfunction "RING_1_3") (pintype "passive"))
    )
    (net (code "17") (name "/J1.2") (class "Default")
      (node (ref "J1") (pin "2") (pinfunction "Analog_In_2") (pintype "passive"))
    )
    (net (code "18") (name "/J1.3") (class "Default")
      (node (ref "J1") (pin "3") (pinfunction "LP_UART_RX_3") (pintype "passive"))
    )
    (net (code "19") (name "/J1.4") (class "Default")
      (node (ref "J1") (pin "4") (pinfunction "LP_UART_TX_4") (pintype "passive"))
    )
    (net (code "20") (name "/J1.8") (class "Default")
      (node (ref "J1") (pin "8") (pinfunction "GPIO_!_8") (pintype "passive"))
    )
    (net (code "21") (name "/J1.9") (class "Default")
      (node (ref "J1") (pin "9") (pinfunction "I2C_SCL_9") (pintype "passive"))
    )
    (net (code "22") (name "/J1.10") (class "Default")
      (node (ref "J1") (pin "10") (pinfunction "I2C_SDA_10") (pintype "passive"))
    )
    (net (code "23") (name "/J2.11") (class "Default")
      (node (ref "J1") (pin "11") (pinfunction "GPIO_!_11") (pintype "passive"))
    )
    (net (code "24") (name "/J2.14") (class "Default")
      (node (ref "J1") (pin "14") (pinfunction "SPI_MISO_14") (pintype "passive"))
    )
    (net (code "25") (name "/J2.16") (class "Default")
      (node (ref "J1") (pin "16") (pinfunction "RST_16") (pintype "passive"))
    )
    (net (code "26") (name "/J2.17") (class "Default")
      (node (ref "J1") (pin "17") (pinfunction "GPIO_17") (pintype "passive"))
    )
    (net (code "27") (name "/J2.18") (class "Default")
      (node (ref "J1") (pin "18") (pinfunction "GPIO_!_18") (pintype "passive"))
    )
    (net (code "28") (name "/J3.23") (class "Default")
      (node (ref "J1") (pin "23") (pinfunction "Analog_In_23") (pintype "passive"))
    )
    (net (code "29") (name "/J3.24") (class "Default")
      (node (ref "J1") (pin "24") (pinfunction "Analog_In_24") (pintype "passive"))
    )
    (net (code "30") (name "/J3.25") (class "Default")
      (node (ref "J1") (pin "25") (pinfunction "Analog_In_25") (pintype "passive"))
    )
    (net (code "31") (name "/J3.27") (class "Default")
      (node (ref "J1") (pin "27") (pinfunction "Analog_In/I2S_WS_27") (pintype "passive"))
    )
    (net (code "32") (name "/J3.28") (class "Default")
      (node (ref "J1") (pin "28") (pinfunction "Analog_In/I2S_SCLK_28") (pintype "passive"))
    )
    (net (code "33") (name "/J3.29") (class "Default")
      (node (ref "J1") (pin "29") (pinfunction "Analog_Out/I2S_SDout_29") (pintype "passive"))
    )
    (net (code "34") (name "/J4.32") (class "Default")
      (node (ref "J1") (pin "32") (pinfunction "GPIO_!_32") (pintype "passive"))
    )
    (net (code "35") (name "/J4.33") (class "Default")
      (node (ref "J1") (pin "33") (pinfunction "GPIO_!_33") (pintype "passive"))
    )
    (net (code "36") (name "/J4.34") (class "Default")
      (node (ref "J1") (pin "34") (pinfunction "GPIO_!_34") (pintype "passive"))
    )
    (net (code "37") (name "/J4.35") (class "Default")
      (node (ref "J1") (pin "35") (pinfunction "Timer_Cap/GPIO_!_35") (pintype "passive"))
    )
    (net (code "38") (name "/J4.36") (class "Default")
      (node (ref "J1") (pin "36") (pinfunction "Timer_Cap/GPIO_!_36") (pintype "passive"))
    )
    (net (code "39") (name "/J4.37") (class "Default")
      (node (ref "J1") (pin "37") (pinfunction "PWM/GPIO_!_37") (pintype "passive"))
    )
    (net (code "40") (name "/J4.40") (class "Default")
      (node (ref "J1") (pin "40") (pinfunction "PWM/GPIO_!_40") (pintype "passive"))
    )
    (net (code "41") (name "/LAUNCHPAD_DAC_OUT") (class "Default")
      (node (ref "J1") (pin "30") (pinfunction "Analog_Out/I2S_SDin_30") (pintype "passive"))
      (node (ref "J5") (pin "3") (pinfunction "3_3") (pintype "passive"))
    )
    (net (code "42") (name "/LOUDSPEAKER_OUT+") (class "Default")
      (node (ref "C1") (pin "1") (pinfunction "+_1") (pintype "passive"))
      (node (ref "U3") (pin "3") (pinfunction "NC2_3") (pintype "passive"))
    )
    (net (code "43") (name "/LOUDSPEAKER_OUT-") (class "Default")
      (node (ref "S1") (pin "2") (pinfunction "BLK-_2") (pintype "passive"))
      (node (ref "U3") (pin "15") (pinfunction "NC1_15") (pintype "passive"))
    )
    (net (code "44") (name "/MIC_DET") (class "Default")
      (node (ref "R15") (pin "2") (pinfunction "2_2") (pintype "passive"))
      (node (ref "R18") (pin "1") (pinfunction "1_1") (pintype "passive"))
      (node (ref "TP1") (pin "1") (pintype "passive"))
      (node (ref "U3") (pin "8") (pinfunction "IN3-4_8") (pintype "input"))
    )
    (net (code "45") (name "/MIC_OUT") (class "Default")
      (node (ref "C20") (pin "1") (pinfunction "1_1") (pintype "passive"))
      (node (ref "R36") (pin "2") (pinfunction "2_2") (pintype "passive"))
      (node (ref "R4") (pin "1") (pinfunction "1_1") (pintype "passive"))
      (node (ref "R5") (pin "1") (pinfunction "1_1") (pintype "passive"))
    )
    (net (code "46") (name "/MIC_OUT_ALT") (class "Default")
      (node (ref "J1") (pin "26") (pinfunction "Analog_In_26") (pintype "passive"))
      (node (ref "R5") (pin "2") (pinfunction "2_2") (pintype "passive"))
    )
    (net (code "47") (name "/MIC_OUT_PRI") (class "Default")
      (node (ref "J1") (pin "6") (pinfunction "Analog_In_6") (pintype "passive"))
      (node (ref "R4") (pin "2") (pinfunction "2_2") (pintype "passive"))
    )
    (net (code "48") (name "/MIC_PWR") (class "Default")
      (node (ref "C14") (pin "1") (pinfunction "+_1") (pintype "passive"))
      (node (ref "C15") (pin "1") (pinfunction "1_1") (pintype "passive"))
      (node (ref "R1") (pin "1") (pinfunction "1_1") (pintype "passive"))
      (node (ref "R3") (pin "1") (pinfunction "1_1") (pintype "passive"))
      (node (ref "R30") (pin "1") (pinfunction "1_1") (pintype "passive"))
      (node (ref "R32") (pin "2") (pinfunction "2_2") (pintype "passive"))
      (node (ref "U5") (pin "5") (pinfunction "~{SHDN}_5") (pintype "input"))
      (node (ref "U5") (pin "6") (pinfunction "VDD_6") (pintype "power_in"))
    )
    (net (code "49") (name "/MIC_PWR_ALT") (class "Default")
      (node (ref "J1") (pin "31") (pinfunction "GPIO_!_31") (pintype "passive"))
      (node (ref "R3") (pin "2") (pinfunction "2_2") (pintype "passive"))
    )
    (net (code "50") (name "/MIC_PWR_PRI") (class "Default")
      (node (ref "J1") (pin "5") (pinfunction "GPIO_!_5") (pintype "passive"))
      (node (ref "R1") (pin "2") (pinfunction "2_2") (pintype "passive"))
    )
    (net (code "51") (name "/MIC_RAW") (class "Default")
      (node (ref "C19") (pin "1") (pinfunction "1_1") (pintype "passive"))
      (node (ref "R34") (pin "1") (pinfunction "1_1") (pintype "passive"))
      (node (ref "U3") (pin "10") (pinfunction "COM4_10") (pintype "passive"))
    )
    (net (code "52") (name "/ONBOARD_DAC_OUT") (class "Default")
      (node (ref "J5") (pin "1") (pinfunction "1_1") (pintype "passive"))
      (node (ref "U2") (pin "6") (pinfunction "VOUT_6") (pintype "tri_state"))
    )
    (net (code "53") (name "/ONBOARD_MIC") (class "Default")
      (node (ref "MIC1") (pin "1") (pinfunction "1_1") (pintype "passive"))
      (node (ref "U3") (pin "9") (pinfunction "NO4_9") (pintype "passive"))
    )
    (net (code "54") (name "/PWM_ALT") (class "Default")
      (node (ref "J1") (pin "39") (pinfunction "PWM/GPIO_!_39") (pintype "passive"))
      (node (ref "R10") (pin "2") (pinfunction "2_2") (pintype "passive"))
    )
    (net (code "55") (name "/PWM_AUDIO") (class "Default")
      (node (ref "R10") (pin "1") (pinfunction "1_1") (pintype "passive"))
      (node (ref "R19") (pin "1") (pinfunction "1_1") (pintype "passive"))
      (node (ref "R9") (pin "1") (pinfunction "1_1") (pintype "passive"))
    )
    (net (code "56") (name "/PWM_PRI") (class "Default")
      (node (ref "J1") (pin "19") (pinfunction "PWM/GPIO_!_19") (pintype "passive"))
      (node (ref "R9") (pin "2") (pinfunction "2_2") (pintype "passive"))
    )
    (net (code "57") (name "/SPEAKER_DET") (class "Default")
      (node (ref "C7") (pin "2") (pinfunction "2_2") (pintype "passive"))
      (node (ref "R21") (pin "2") (pinfunction "2_2") (pintype "passive"))
      (node (ref "R22") (pin "2") (pinfunction "2_2") (pintype "passive"))
      (node (ref "R23") (pin "1") (pinfunction "1_1") (pintype "passive"))
      (node (ref "TP2") (pin "1") (pintype "passive"))
      (node (ref "U1") (pin "5") (pinfunction "DET_TRIGGER_5") (pintype "passive"))
      (node (ref "U3") (pin "16") (pinfunction "IN1-2_16") (pintype "input"))
    )
    (net (code "58") (name "GND") (class "Default")
      (node (ref "C12") (pin "2") (pinfunction "2_2") (pintype "passive"))
      (node (ref "C13") (pin "2") (pinfunction "-_2") (pintype "passive"))
      (node (ref "C14") (pin "2") (pinfunction "-_2") (pintype "passive"))
      (node (ref "C15") (pin "2") (pinfunction "2_2") (pintype "passive"))
      (node (ref "C16") (pin "1") (pinfunction "1_1") (pintype "passive"))
      (node (ref "C17") (pin "1") (pinfunction "1_1") (pintype "passive"))
      (node (ref "C18") (pin "2") (pinfunction "2_2") (pintype "passive"))
      (node (ref "C20") (pin "2") (pinfunction "2_2") (pintype "passive"))
      (node (ref "C22") (pin "1") (pinfunction "1_1") (pintype "passive"))
      (node (ref "C3") (pin "1") (pinfunction "1_1") (pintype "passive"))
      (node (ref "C4") (pin "2") (pinfunction "2_2") (pintype "passive"))
      (node (ref "C5") (pin "2") (pinfunction "2_2") (pintype "passive"))
      (node (ref "C6") (pin "2") (pinfunction "2_2") (pintype "passive"))
      (node (ref "C7") (pin "1") (pinfunction "1_1") (pintype "passive"))
      (node (ref "C8") (pin "1") (pinfunction "1_1") (pintype "passive"))
      (node (ref "J1") (pin "20") (pinfunction "GND_20") (pintype "power_in"))
      (node (ref "J1") (pin "22") (pinfunction "GND_22") (pintype "power_in"))
      (node (ref "MIC1") (pin "2") (pinfunction "2_2") (pintype "passive"))
      (node (ref "R11") (pin "1") (pinfunction "1_1") (pintype "passive"))
      (node (ref "R17") (pin "2") (pinfunction "2_2") (pintype "passive"))
      (node (ref "R2") (pin "2") (pinfunction "2_2") (pintype "passive"))
      (node (ref "R20") (pin "2") (pinfunction "2_2") (pintype "passive"))
      (node (ref "R23") (pin "2") (pinfunction "2_2") (pintype "passive"))
      (node (ref "R27") (pin "GND") (pinfunction "MT_GND") (pintype "passive"))
      (node (ref "R37") (pin "1") (pinfunction "1_1") (pintype "passive"))
      (node (ref "R38") (pin "1") (pinfunction "1_1") (pintype "passive"))
      (node (ref "R7") (pin "2") (pinfunction "2_2") (pintype "passive"))
      (node (ref "U1") (pin "10") (pinfunction "GND_10") (pintype "passive"))
      (node (ref "U1") (pin "17") (pinfunction "PAD_17") (pintype "passive"))
      (node (ref "U1") (pin "3") (pinfunction "GND_3") (pintype "passive"))
      (node (ref "U1") (pin "4") (pinfunction "ADDR_SEL_4") (pintype "passive"))
      (node (ref "U2") (pin "5") (pinfunction "GND_5") (pintype "power_in"))
      (node (ref "U3") (pin "4") (pinfunction "GND_4") (pintype "power_in"))
      (node (ref "U4") (pin "7") (pinfunction "GND_7") (pintype "power_in"))
      (node (ref "U4") (pin "9") (pinfunction "EP_9") (pintype "passive"))
      (node (ref "U5") (pin "2") (pinfunction "GND_2") (pintype "power_in"))
    )
    (net (code "59") (name "Net-(C1--)") (class "Default")
      (node (ref "C1") (pin "2") (pinfunction "-_2") (pintype "passive"))
      (node (ref "S1") (pin "1") (pinfunction "RED+_1") (pintype "passive"))
    )
    (net (code "60") (name "Net-(C6-Pad1)") (class "Default")
      (node (ref "C6") (pin "1") (pinfunction "1_1") (pintype "passive"))
      (node (ref "J5") (pin "5") (pinfunction "5_5") (pintype "passive"))
      (node (ref "R19") (pin "2") (pinfunction "2_2") (pintype "passive"))
    )
    (net (code "61") (name "Net-(C8-Pad2)") (class "Default")
      (node (ref "C8") (pin "2") (pinfunction "2_2") (pintype "passive"))
      (node (ref "R24") (pin "2") (pinfunction "2_2") (pintype "passive"))
    )
    (net (code "62") (name "Net-(C11-Pad1)") (class "Default")
      (node (ref "C11") (pin "1") (pinfunction "1_1") (pintype "passive"))
      (node (ref "R29") (pin "1") (pinfunction "1_1") (pintype "passive"))
    )
    (net (code "63") (name "Net-(C13-+)") (class "Default")
      (node (ref "C13") (pin "1") (pinfunction "+_1") (pintype "passive"))
      (node (ref "R30") (pin "2") (pinfunction "2_2") (pintype "passive"))
      (node (ref "R34") (pin "2") (pinfunction "2_2") (pintype "passive"))
    )
    (net (code "64") (name "Net-(C21-Pad1)") (class "Default")
      (node (ref "C21") (pin "1") (pinfunction "1_1") (pintype "passive"))
      (node (ref "R37") (pin "2") (pinfunction "2_2") (pintype "passive"))
    )
    (net (code "65") (name "Net-(C22-Pad2)") (class "Default")
      (node (ref "C22") (pin "2") (pinfunction "2_2") (pintype "passive"))
      (node (ref "R32") (pin "1") (pinfunction "1_1") (pintype "passive"))
      (node (ref "R35") (pin "2") (pinfunction "2_2") (pintype "passive"))
    )
    (net (code "66") (name "Net-(J5-Pad2)") (class "Default")
      (node (ref "J5") (pin "2") (pinfunction "2_2") (pintype "passive"))
      (node (ref "J5") (pin "4") (pinfunction "4_4") (pintype "passive"))
      (node (ref "R12") (pin "1") (pinfunction "1_1") (pintype "passive"))
    )
    (net (code "67") (name "Net-(J6-RING_2)") (class "Default")
      (node (ref "J6") (pin "4") (pinfunction "RING_2_4") (pintype "passive"))
      (node (ref "U1") (pin "14") (pinfunction "RING2_SENSE_14") (pintype "passive"))
      (node (ref "U1") (pin "7") (pinfunction "RING2_7") (pintype "passive"))
    )
    (net (code "68") (name "Net-(J6-SLEEVE)") (class "Default")
      (node (ref "J6") (pin "1") (pinfunction "SLEEVE_1") (pintype "passive"))
      (node (ref "U1") (pin "15") (pinfunction "SLEEVE_SENSE_15") (pintype "passive"))
      (node (ref "U1") (pin "6") (pinfunction "SLEEVE_6") (pintype "passive"))
    )
    (net (code "69") (name "Net-(J6-TIP_SWITCH)") (class "Default")
      (node (ref "J6") (pin "5") (pinfunction "TIP_SWITCH_5") (pintype "passive"))
      (node (ref "R21") (pin "1") (pinfunction "1_1") (pintype "passive"))
    )
    (net (code "70") (name "Net-(R27-A1)") (class "Default")
      (node (ref "R25") (pin "2") (pinfunction "2_2") (pintype "passive"))
      (node (ref "R27") (pin "1") (pinfunction "A1_1") (pintype "passive"))
    )
    (net (code "71") (name "Net-(U1-MICn)") (class "Default")
      (node (ref "R11") (pin "2") (pinfunction "2_2") (pintype "passive"))
      (node (ref "U1") (pin "12") (pinfunction "MICn_12") (pintype "passive"))
    )
    (net (code "72") (name "Net-(U1-{slash}MIC_PRESENT)") (class "Default")
      (node (ref "R18") (pin "2") (pinfunction "2_2") (pintype "passive"))
      (node (ref "U1") (pin "8") (pinfunction "/MIC_PRESENT_8") (pintype "passive"))
    )
    (net (code "73") (name "Net-(U2-DIN)") (class "Default")
      (node (ref "R14") (pin "2") (pinfunction "2_2") (pintype "passive"))
      (node (ref "U2") (pin "3") (pinfunction "DIN_3") (pintype "input"))
    )
    (net (code "74") (name "Net-(U2-SCLK)") (class "Default")
      (node (ref "R13") (pin "2") (pinfunction "2_2") (pintype "passive"))
      (node (ref "U2") (pin "2") (pinfunction "SCLK_2") (pintype "input"))
    )
    (net (code "75") (name "Net-(U2-~{SYNC})") (class "Default")
      (node (ref "R16") (pin "2") (pinfunction "2_2") (pintype "passive"))
      (node (ref "U2") (pin "1") (pinfunction "~{SYNC}_1") (pintype "input"))
    )
    (net (code "76") (name "Net-(U3-COM3)") (class "Default")
      (node (ref "R2") (pin "1") (pinfunction "1_1") (pintype "passive"))
      (node (ref "U3") (pin "6") (pinfunction "COM3_6") (pintype "passive"))
    )
    (net (code "77") (name "Net-(U3-NC3)") (class "Default")
      (node (ref "R20") (pin "1") (pinfunction "1_1") (pintype "passive"))
      (node (ref "U3") (pin "7") (pinfunction "NC3_7") (pintype "passive"))
    )
    (net (code "78") (name "Net-(U3-NO3)") (class "Default")
      (node (ref "R7") (pin "1") (pinfunction "1_1") (pintype "passive"))
      (node (ref "U3") (pin "5") (pinfunction "NO3_5") (pintype "passive"))
    )
    (net (code "79") (name "Net-(U4-BYPASS)") (class "Default")
      (node (ref "C12") (pin "1") (pinfunction "1_1") (pintype "passive"))
      (node (ref "U4") (pin "2") (pinfunction "BYPASS_2") (pintype "passive"))
      (node (ref "U4") (pin "3") (pinfunction "IN+_3") (pintype "input"))
    )
    (net (code "80") (name "Net-(U4-IN-)") (class "Default")
      (node (ref "C10") (pin "1") (pinfunction "1_1") (pintype "passive"))
      (node (ref "R25") (pin "1") (pinfunction "1_1") (pintype "passive"))
      (node (ref "R29") (pin "2") (pinfunction "2_2") (pintype "passive"))
      (node (ref "U4") (pin "4") (pinfunction "IN-_4") (pintype "input"))
    )
    (net (code "81") (name "Net-(U5-IN+)") (class "Default")
      (node (ref "C19") (pin "2") (pinfunction "2_2") (pintype "passive"))
      (node (ref "R35") (pin "1") (pinfunction "1_1") (pintype "passive"))
      (node (ref "R38") (pin "2") (pinfunction "2_2") (pintype "passive"))
      (node (ref "U5") (pin "3") (pinfunction "IN+_3") (pintype "input"))
    )
    (net (code "82") (name "Net-(U5-IN-)") (class "Default")
      (node (ref "C9") (pin "1") (pinfunction "1_1") (pintype "passive"))
      (node (ref "R24") (pin "1") (pinfunction "1_1") (pintype "passive"))
      (node (ref "R26") (pin "1") (pinfunction "1_1") (pintype "passive"))
      (node (ref "U5") (pin "4") (pinfunction "IN-_4") (pintype "input"))
    )
    (net (code "83") (name "Net-(U5-OUT)") (class "Default")
      (node (ref "C9") (pin "2") (pinfunction "2_2") (pintype "passive"))
      (node (ref "R26") (pin "2") (pinfunction "2_2") (pintype "passive"))
      (node (ref "R36") (pin "1") (pinfunction "1_1") (pintype "passive"))
      (node (ref "U5") (pin "1") (pinfunction "OUT_1") (pintype "tri_state"))
    )
    (net (code "84") (name "unconnected-(J6-RING_SWITCH-Pad6)") (class "Default")
      (node (ref "J6") (pin "6") (pinfunction "RING_SWITCH_6") (pintype "passive+no_connect"))
    )
  )
)
